# design.net
KiCad netlist of a schematic drawn in Altium Designer
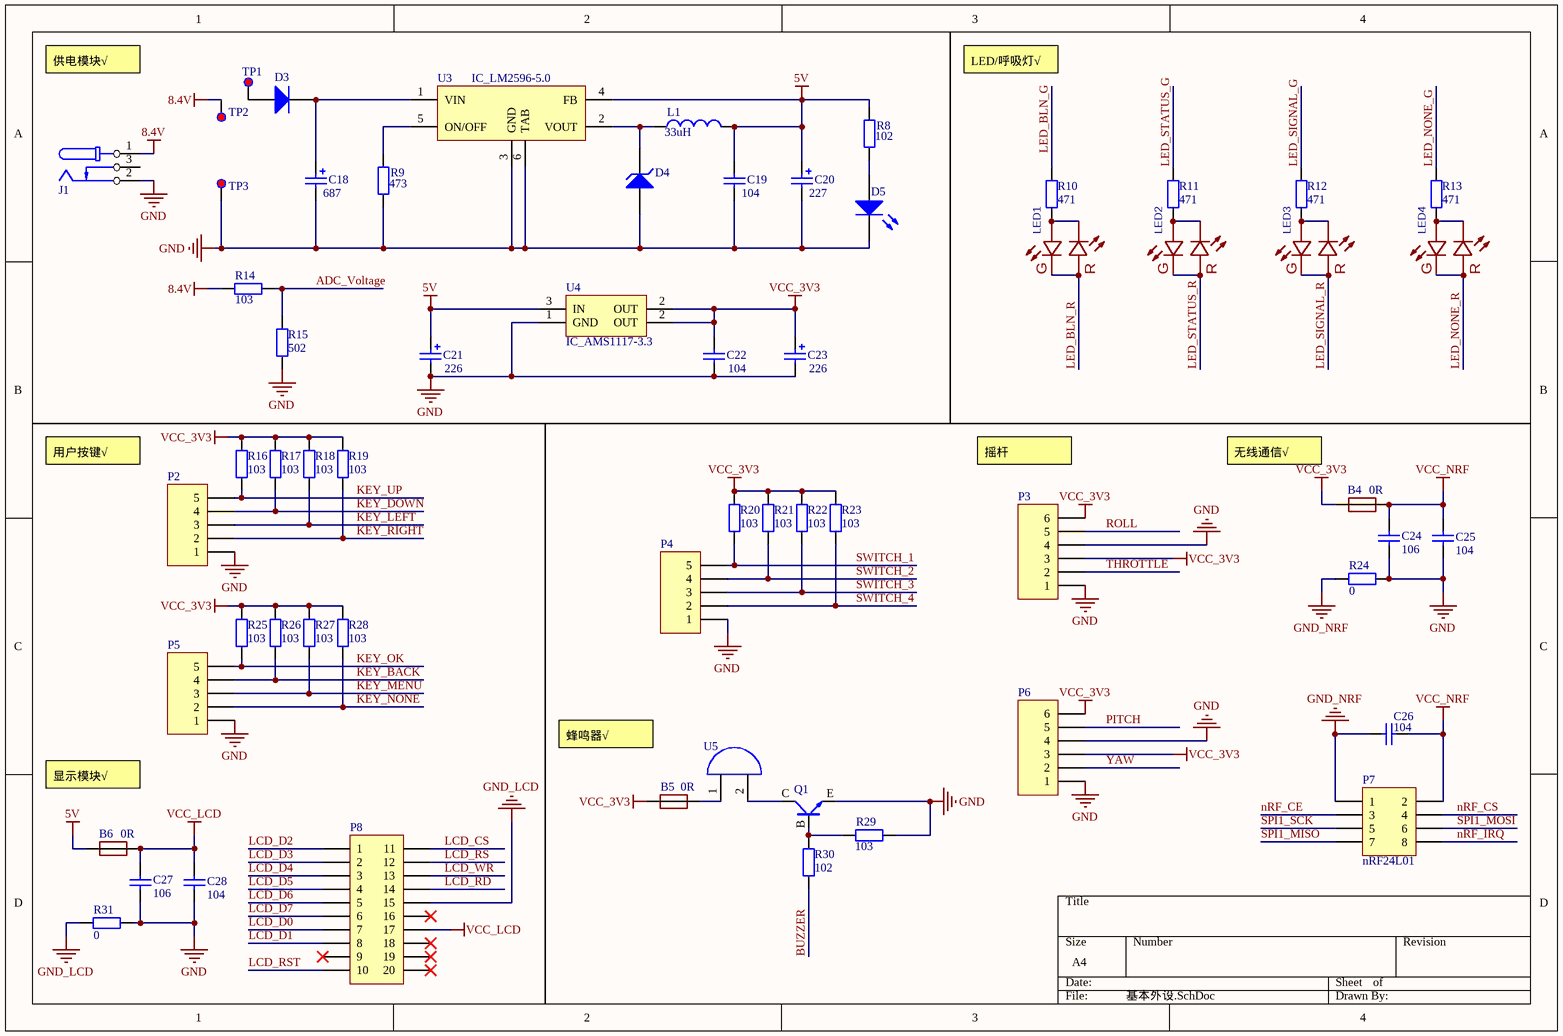
[diagram p0: 基本外设.SchDoc]

(export (version "E")
  (design (tool "Eeschema 10.0.6"))
  (components
    (comp (ref "B4")
      (value "0R")
      (footprint "CC1608-0603")
      (description "磁珠")
      (fields (field (name "Comment") "MPZ1608S101ATDH5"))
      (libsource (lib "SCHLIB") (part "FB_BEAD"))
    )
    (comp (ref "B5")
      (value "0R")
      (footprint "CC1608-0603")
      (description "磁珠")
      (fields (field (name "Comment") "MPZ1608S101ATDH5"))
      (libsource (lib "") (part "FB_BEAD_1"))
    )
    (comp (ref "B6")
      (value "0R")
      (footprint "CC1608-0603")
      (description "磁珠")
      (fields (field (name "Comment") "MPZ1608S101ATDH5"))
      (libsource (lib "SCHLIB") (part "FB_BEAD"))
    )
    (comp (ref "C18")
      (value "687")
      (footprint "CDT-10")
      (description "Polarized Capacitor (Axial)")
      (fields (field (name "Comment") "Cap Pol2") (field (name "PUBLISHER") "Altium Limited"))
      (libsource (lib "Miscellaneous Devices") (part "Cap Pol2"))
    )
    (comp (ref "C19")
      (value "104")
      (footprint "CC1608-0603")
      (description "Capacitor")
      (fields (field (name "Comment") "Cap") (field (name "PUBLISHER") "Altium Limited"))
      (libsource (lib "Miscellaneous Devices") (part "Cap"))
    )
    (comp (ref "C20")
      (value "227")
      (footprint "CDT-6.3")
      (description "Polarized Capacitor (Axial)")
      (fields (field (name "Comment") "Cap Pol2") (field (name "PUBLISHER") "Altium Limited"))
      (libsource (lib "Miscellaneous Devices") (part "Cap Pol2"))
    )
    (comp (ref "C21")
      (value "226")
      (footprint "CDT-5")
      (description "Polarized Capacitor (Axial)")
      (fields (field (name "Comment") "Cap Pol2") (field (name "PUBLISHER") "Altium Limited"))
      (libsource (lib "Miscellaneous Devices") (part "Cap Pol2"))
    )
    (comp (ref "C22")
      (value "104")
      (footprint "CC1608-0603")
      (description "Capacitor")
      (fields (field (name "Comment") "Cap") (field (name "PUBLISHER") "Altium Limited"))
      (libsource (lib "Miscellaneous Devices") (part "Cap"))
    )
    (comp (ref "C23")
      (value "226")
      (footprint "CDT-5")
      (description "Polarized Capacitor (Axial)")
      (fields (field (name "Comment") "Cap Pol2") (field (name "PUBLISHER") "Altium Limited"))
      (libsource (lib "Miscellaneous Devices") (part "Cap Pol2"))
    )
    (comp (ref "C24")
      (value "106")
      (footprint "CC1608-0603")
      (description "Capacitor")
      (fields (field (name "Comment") "Cap") (field (name "PUBLISHER") "Altium Limited"))
      (libsource (lib "Miscellaneous Devices") (part "Cap"))
    )
    (comp (ref "C25")
      (value "104")
      (footprint "CC1608-0603")
      (description "Capacitor")
      (fields (field (name "Comment") "Cap") (field (name "PUBLISHER") "Altium Limited"))
      (libsource (lib "Miscellaneous Devices") (part "Cap"))
    )
    (comp (ref "C26")
      (value "104")
      (footprint "CC1608-0603")
      (description "Capacitor")
      (fields (field (name "Comment") "Cap") (field (name "PUBLISHER") "Altium Limited"))
      (libsource (lib "Miscellaneous Devices") (part "Cap"))
    )
    (comp (ref "C27")
      (value "106")
      (footprint "CC1608-0603")
      (description "Capacitor")
      (fields (field (name "Comment") "Cap") (field (name "PUBLISHER") "Altium Limited"))
      (libsource (lib "Miscellaneous Devices") (part "Cap"))
    )
    (comp (ref "C28")
      (value "104")
      (footprint "CC1608-0603")
      (description "Capacitor")
      (fields (field (name "Comment") "Cap") (field (name "PUBLISHER") "Altium Limited"))
      (libsource (lib "Miscellaneous Devices") (part "Cap"))
    )
    (comp (ref "D3")
      (value "Diode")
      (footprint "DO-214AC(SMA)-D")
      (description "Default Diode")
      (fields (field (name "PUBLISHER") "Altium Limited"))
      (libsource (lib "Miscellaneous Devices") (part "Diode"))
    )
    (comp (ref "D4")
      (value "D Zener")
      (footprint "DO-214AC(SMA)-T")
      (description "Zener Diode")
      (fields (field (name "PUBLISHER") "Altium Limited"))
      (libsource (lib "Miscellaneous Devices") (part "D Zener"))
    )
    (comp (ref "D5")
      (value "LED0")
      (footprint "CD1608-0603")
      (description "Typical INFRARED GaAs LED")
      (fields (field (name "PUBLISHER") "Altium Limited"))
      (libsource (lib "Miscellaneous Devices") (part "LED0"))
    )
    (comp (ref "J1")
      (value "PT_POWERJACK")
      (footprint "DC2.2")
      (description "DC端子")
      (libsource (lib "SCHLIB") (part "PT_POWERJACK"))
    )
    (comp (ref "L1")
      (value "33uH")
      (footprint "L7.3X7.3X4.5")
      (description "Inductor")
      (fields (field (name "PUBLISHER") "Altium Limited"))
      (libsource (lib "Miscellaneous Devices") (part "Inductor"))
    )
    (comp (ref "LED1")
      (value "DX_LED_无极")
      (footprint "LED_无极")
      (description "无极双色发光二极管")
      (fields
        (field (name "BOM_SUPPLIER PART") "C440436")
        (field (name "BOM_MANUFACTURER PART") "TJ-L5FYTXHMNPLC2R7K-A5")
        (field (name "CONTRIBUTOR") "LCSC")
      )
      (libsource (lib "SCHLIB") (part "DX_LED_无极"))
    )
    (comp (ref "LED2")
      (value "DX_LED_无极")
      (footprint "LED_无极")
      (description "无极双色发光二极管")
      (fields
        (field (name "BOM_SUPPLIER PART") "C440436")
        (field (name "BOM_MANUFACTURER PART") "TJ-L5FYTXHMNPLC2R7K-A5")
        (field (name "CONTRIBUTOR") "LCSC")
      )
      (libsource (lib "SCHLIB") (part "DX_LED_无极"))
    )
    (comp (ref "LED3")
      (value "DX_LED_无极")
      (footprint "LED_无极")
      (description "无极双色发光二极管")
      (fields
        (field (name "BOM_SUPPLIER PART") "C440436")
        (field (name "BOM_MANUFACTURER PART") "TJ-L5FYTXHMNPLC2R7K-A5")
        (field (name "CONTRIBUTOR") "LCSC")
      )
      (libsource (lib "SCHLIB") (part "DX_LED_无极"))
    )
    (comp (ref "LED4")
      (value "DX_LED_无极")
      (footprint "LED_无极")
      (description "无极双色发光二极管")
      (fields
        (field (name "BOM_SUPPLIER PART") "C440436")
        (field (name "BOM_MANUFACTURER PART") "TJ-L5FYTXHMNPLC2R7K-A5")
        (field (name "CONTRIBUTOR") "LCSC")
      )
      (libsource (lib "SCHLIB") (part "DX_LED_无极"))
    )
    (comp (ref "P2")
      (value "Header 5")
      (footprint "XHT_1.25_SMD_5p")
      (description "Header, 5-Pin")
      (fields (field (name "PUBLISHER") "Altium Limited"))
      (libsource (lib "Miscellaneous Connectors") (part "Header 5"))
    )
    (comp (ref "P3")
      (value "Header 6")
      (footprint "XHT_2.0_SMD_6P")
      (description "Header, 6-Pin")
      (fields (field (name "PUBLISHER") "Altium Limited"))
      (libsource (lib "Miscellaneous Connectors") (part "Header 6"))
    )
    (comp (ref "P4")
      (value "Header 6")
      (footprint "XHT_1.25_SMD_5p")
      (description "Header, 5-Pin")
      (fields (field (name "PUBLISHER") "Altium Limited"))
      (libsource (lib "Miscellaneous Connectors") (part "Header 5"))
    )
    (comp (ref "P5")
      (value "Header 5")
      (footprint "XHT_1.25_SMD_5p")
      (description "Header, 5-Pin")
      (fields (field (name "PUBLISHER") "Altium Limited"))
      (libsource (lib "Miscellaneous Connectors") (part "Header 5"))
    )
    (comp (ref "P6")
      (value "Header 6")
      (footprint "XHT_2.0_SMD_6P")
      (description "Header, 6-Pin")
      (fields (field (name "PUBLISHER") "Altium Limited"))
      (libsource (lib "Miscellaneous Connectors") (part "Header 6"))
    )
    (comp (ref "P7")
      (value "nRF24L01")
      (footprint "HDR2X4")
      (description "Header, 4-Pin, Dual row")
      (fields (field (name "PUBLISHER") "Altium Limited"))
      (libsource (lib "Miscellaneous Connectors") (part "Header 4X2"))
    )
    (comp (ref "P8")
      (value "Header 10X2A")
      (footprint "LCD_2.4_TFT")
      (description "Header, 10-Pin, Dual row")
      (fields (field (name "PUBLISHER") "Altium Limited"))
      (libsource (lib "Miscellaneous Connectors") (part "Header 10X2A"))
    )
    (comp (ref "Q1")
      (value "TX_NPN")
      (footprint "SOT-23-3T")
      (description "NPN三极管")
      (libsource (lib "SCHLIB") (part "TX_NPN"))
    )
    (comp (ref "R8")
      (value "102")
      (footprint "CC1608-0603")
      (description "Resistor")
      (fields (field (name "Comment") "Res2") (field (name "PUBLISHER") "Altium Limited"))
      (libsource (lib "") (part "Res2_2"))
    )
    (comp (ref "R9")
      (value "473")
      (footprint "CC1608-0603")
      (description "Resistor")
      (fields (field (name "Comment") "Res2") (field (name "PUBLISHER") "Altium Limited"))
      (libsource (lib "") (part "Res2_2"))
    )
    (comp (ref "R10")
      (value "471")
      (footprint "CC1608-0603")
      (description "电阻")
      (fields (field (name "Comment") "RX_RES"))
      (libsource (lib "") (part "RX_RES_2"))
    )
    (comp (ref "R11")
      (value "471")
      (footprint "CC1608-0603")
      (description "电阻")
      (fields (field (name "Comment") "RX_RES"))
      (libsource (lib "") (part "RX_RES_2"))
    )
    (comp (ref "R12")
      (value "471")
      (footprint "CC1608-0603")
      (description "电阻")
      (fields (field (name "Comment") "RX_RES"))
      (libsource (lib "") (part "RX_RES_2"))
    )
    (comp (ref "R13")
      (value "471")
      (footprint "CC1608-0603")
      (description "电阻")
      (fields (field (name "Comment") "RX_RES"))
      (libsource (lib "") (part "RX_RES_2"))
    )
    (comp (ref "R14")
      (value "103")
      (footprint "CC1608-0603")
      (description "Resistor")
      (fields (field (name "Comment") "Res2") (field (name "PUBLISHER") "Altium Limited"))
      (libsource (lib "") (part "Res2_1"))
    )
    (comp (ref "R15")
      (value "502")
      (footprint "CC1608-0603")
      (description "Resistor")
      (fields (field (name "Comment") "Res2") (field (name "PUBLISHER") "Altium Limited"))
      (libsource (lib "Miscellaneous Devices") (part "Res2"))
    )
    (comp (ref "R16")
      (value "103")
      (footprint "CC1608-0603")
      (description "电阻")
      (fields (field (name "Comment") "RX_RES"))
      (libsource (lib "SCHLIB") (part "RX_RES"))
    )
    (comp (ref "R17")
      (value "103")
      (footprint "CC1608-0603")
      (description "电阻")
      (fields (field (name "Comment") "RX_RES"))
      (libsource (lib "SCHLIB") (part "RX_RES"))
    )
    (comp (ref "R18")
      (value "103")
      (footprint "CC1608-0603")
      (description "电阻")
      (fields (field (name "Comment") "RX_RES"))
      (libsource (lib "SCHLIB") (part "RX_RES"))
    )
    (comp (ref "R19")
      (value "103")
      (footprint "CC1608-0603")
      (description "电阻")
      (fields (field (name "Comment") "RX_RES"))
      (libsource (lib "SCHLIB") (part "RX_RES"))
    )
    (comp (ref "R20")
      (value "103")
      (footprint "CC1608-0603")
      (description "电阻")
      (fields (field (name "Comment") "RX_RES"))
      (libsource (lib "SCHLIB") (part "RX_RES"))
    )
    (comp (ref "R21")
      (value "103")
      (footprint "CC1608-0603")
      (description "电阻")
      (fields (field (name "Comment") "RX_RES"))
      (libsource (lib "SCHLIB") (part "RX_RES"))
    )
    (comp (ref "R22")
      (value "103")
      (footprint "CC1608-0603")
      (description "电阻")
      (fields (field (name "Comment") "RX_RES"))
      (libsource (lib "SCHLIB") (part "RX_RES"))
    )
    (comp (ref "R23")
      (value "103")
      (footprint "CC1608-0603")
      (description "电阻")
      (fields (field (name "Comment") "RX_RES"))
      (libsource (lib "SCHLIB") (part "RX_RES"))
    )
    (comp (ref "R24")
      (value "0")
      (footprint "CC1608-0603")
      (description "电阻")
      (fields (field (name "Comment") "RX_RES"))
      (libsource (lib "") (part "RX_RES_1"))
    )
    (comp (ref "R25")
      (value "103")
      (footprint "CC1608-0603")
      (description "电阻")
      (fields (field (name "Comment") "RX_RES"))
      (libsource (lib "SCHLIB") (part "RX_RES"))
    )
    (comp (ref "R26")
      (value "103")
      (footprint "CC1608-0603")
      (description "电阻")
      (fields (field (name "Comment") "RX_RES"))
      (libsource (lib "SCHLIB") (part "RX_RES"))
    )
    (comp (ref "R27")
      (value "103")
      (footprint "CC1608-0603")
      (description "电阻")
      (fields (field (name "Comment") "RX_RES"))
      (libsource (lib "SCHLIB") (part "RX_RES"))
    )
    (comp (ref "R28")
      (value "103")
      (footprint "CC1608-0603")
      (description "电阻")
      (fields (field (name "Comment") "RX_RES"))
      (libsource (lib "SCHLIB") (part "RX_RES"))
    )
    (comp (ref "R29")
      (value "103")
      (footprint "CC1608-0603")
      (description "电阻")
      (fields (field (name "Comment") "RX_RES"))
      (libsource (lib "") (part "RX_RES_3"))
    )
    (comp (ref "R30")
      (value "102")
      (footprint "CC1608-0603")
      (description "电阻")
      (fields (field (name "Comment") "RX_RES"))
      (libsource (lib "") (part "RX_RES_2"))
    )
    (comp (ref "R31")
      (value "0")
      (footprint "CC1608-0603")
      (description "电阻")
      (fields (field (name "Comment") "RX_RES"))
      (libsource (lib "") (part "RX_RES_1"))
    )
    (comp (ref "TP1")
      (value "PT_TESTPOINT")
      (footprint "TP-SMD")
      (description "测试点")
      (libsource (lib "SCHLIB") (part "PT_TESTPOINT"))
    )
    (comp (ref "TP2")
      (value "PT_TESTPOINT")
      (footprint "TP-SMD")
      (description "测试点")
      (libsource (lib "SCHLIB") (part "PT_TESTPOINT"))
    )
    (comp (ref "TP3")
      (value "PT_TESTPOINT")
      (footprint "TP-SMD")
      (description "测试点")
      (libsource (lib "SCHLIB") (part "PT_TESTPOINT"))
    )
    (comp (ref "U3")
      (value "IC_LM2596-5.0")
      (footprint "TO-263-5")
      (description "电源芯片")
      (libsource (lib "SCHLIB") (part "IC_LM2596"))
    )
    (comp (ref "U4")
      (value "IC_AMS1117-3.3")
      (footprint "SOT-223")
      (description "电源芯片")
      (libsource (lib "SCHLIB") (part "IC_AMS1117"))
    )
    (comp (ref "U5")
      (value "SC_BEEP")
      (footprint "SC_Buzzer")
      (description "蜂鸣器")
      (libsource (lib "SCHLIB") (part "SC_BEEP"))
    )
  )
  (nets
    (net (code "1") (name "/ADC_Voltage") (class "Default")
      (node (ref "R14") (pin "1") (pinfunction "1_1") (pintype "passive"))
      (node (ref "R15") (pin "1") (pinfunction "1_1") (pintype "passive"))
    )
    (net (code "2") (name "/BUZZER") (class "Default")
      (node (ref "R30") (pin "1") (pinfunction "1_1") (pintype "passive"))
    )
    (net (code "3") (name "/KEY_BACK") (class "Default")
      (node (ref "P5") (pin "4") (pinfunction "4_4") (pintype "passive"))
      (node (ref "R26") (pin "2") (pinfunction "2_2") (pintype "passive"))
    )
    (net (code "4") (name "/KEY_DOWN") (class "Default")
      (node (ref "P2") (pin "4") (pinfunction "4_4") (pintype "passive"))
      (node (ref "R17") (pin "2") (pinfunction "2_2") (pintype "passive"))
    )
    (net (code "5") (name "/KEY_LEFT") (class "Default")
      (node (ref "P2") (pin "3") (pinfunction "3_3") (pintype "passive"))
      (node (ref "R18") (pin "2") (pinfunction "2_2") (pintype "passive"))
    )
    (net (code "6") (name "/KEY_MENU") (class "Default")
      (node (ref "P5") (pin "3") (pinfunction "3_3") (pintype "passive"))
      (node (ref "R27") (pin "2") (pinfunction "2_2") (pintype "passive"))
    )
    (net (code "7") (name "/KEY_NONE") (class "Default")
      (node (ref "P5") (pin "2") (pinfunction "2_2") (pintype "passive"))
      (node (ref "R28") (pin "2") (pinfunction "2_2") (pintype "passive"))
    )
    (net (code "8") (name "/KEY_OK") (class "Default")
      (node (ref "P5") (pin "5") (pinfunction "5_5") (pintype "passive"))
      (node (ref "R25") (pin "2") (pinfunction "2_2") (pintype "passive"))
    )
    (net (code "9") (name "/KEY_RIGHT") (class "Default")
      (node (ref "P2") (pin "2") (pinfunction "2_2") (pintype "passive"))
      (node (ref "R19") (pin "2") (pinfunction "2_2") (pintype "passive"))
    )
    (net (code "10") (name "/KEY_UP") (class "Default")
      (node (ref "P2") (pin "5") (pinfunction "5_5") (pintype "passive"))
      (node (ref "R16") (pin "2") (pinfunction "2_2") (pintype "passive"))
    )
    (net (code "11") (name "/LCD_CS") (class "Default")
      (node (ref "P8") (pin "11") (pinfunction "11_11") (pintype "passive"))
    )
    (net (code "12") (name "/LCD_D0") (class "Default")
      (node (ref "P8") (pin "7") (pinfunction "7_7") (pintype "passive"))
    )
    (net (code "13") (name "/LCD_D1") (class "Default")
      (node (ref "P8") (pin "8") (pinfunction "8_8") (pintype "passive"))
    )
    (net (code "14") (name "/LCD_D2") (class "Default")
      (node (ref "P8") (pin "1") (pinfunction "1_1") (pintype "passive"))
    )
    (net (code "15") (name "/LCD_D3") (class "Default")
      (node (ref "P8") (pin "2") (pinfunction "2_2") (pintype "passive"))
    )
    (net (code "16") (name "/LCD_D4") (class "Default")
      (node (ref "P8") (pin "3") (pinfunction "3_3") (pintype "passive"))
    )
    (net (code "17") (name "/LCD_D5") (class "Default")
      (node (ref "P8") (pin "4") (pinfunction "4_4") (pintype "passive"))
    )
    (net (code "18") (name "/LCD_D6") (class "Default")
      (node (ref "P8") (pin "5") (pinfunction "5_5") (pintype "passive"))
    )
    (net (code "19") (name "/LCD_D7") (class "Default")
      (node (ref "P8") (pin "6") (pinfunction "6_6") (pintype "passive"))
    )
    (net (code "20") (name "/LCD_RD") (class "Default")
      (node (ref "P8") (pin "14") (pinfunction "14_14") (pintype "passive"))
    )
    (net (code "21") (name "/LCD_RS") (class "Default")
      (node (ref "P8") (pin "12") (pinfunction "12_12") (pintype "passive"))
    )
    (net (code "22") (name "/LCD_RST") (class "Default")
      (node (ref "P8") (pin "10") (pinfunction "10_10") (pintype "passive"))
    )
    (net (code "23") (name "/LCD_WR") (class "Default")
      (node (ref "P8") (pin "13") (pinfunction "13_13") (pintype "passive"))
    )
    (net (code "24") (name "/LED_BLN_G") (class "Default")
      (node (ref "R10") (pin "2") (pinfunction "2_2") (pintype "passive"))
    )
    (net (code "25") (name "/LED_BLN_R") (class "Default")
      (node (ref "LED1") (pin "1") (pinfunction "-_1") (pintype "passive"))
    )
    (net (code "26") (name "/LED_NONE_G") (class "Default")
      (node (ref "R13") (pin "2") (pinfunction "2_2") (pintype "passive"))
    )
    (net (code "27") (name "/LED_NONE_R") (class "Default")
      (node (ref "LED4") (pin "1") (pinfunction "-_1") (pintype "passive"))
    )
    (net (code "28") (name "/LED_SIGNAL_G") (class "Default")
      (node (ref "R12") (pin "2") (pinfunction "2_2") (pintype "passive"))
    )
    (net (code "29") (name "/LED_SIGNAL_R") (class "Default")
      (node (ref "LED3") (pin "1") (pinfunction "-_1") (pintype "passive"))
    )
    (net (code "30") (name "/LED_STATUS_G") (class "Default")
      (node (ref "R11") (pin "2") (pinfunction "2_2") (pintype "passive"))
    )
    (net (code "31") (name "/LED_STATUS_R") (class "Default")
      (node (ref "LED2") (pin "1") (pinfunction "-_1") (pintype "passive"))
    )
    (net (code "32") (name "/PITCH") (class "Default")
      (node (ref "P6") (pin "5") (pinfunction "5_5") (pintype "passive"))
    )
    (net (code "33") (name "/ROLL") (class "Default")
      (node (ref "P3") (pin "5") (pinfunction "5_5") (pintype "passive"))
    )
    (net (code "34") (name "/SPI1_MISO") (class "Default")
      (node (ref "P7") (pin "7") (pinfunction "7_7") (pintype "passive"))
    )
    (net (code "35") (name "/SPI1_MOSI") (class "Default")
      (node (ref "P7") (pin "6") (pinfunction "6_6") (pintype "passive"))
    )
    (net (code "36") (name "/SPI1_SCK") (class "Default")
      (node (ref "P7") (pin "5") (pinfunction "5_5") (pintype "passive"))
    )
    (net (code "37") (name "/SWITCH_1") (class "Default")
      (node (ref "P4") (pin "5") (pinfunction "5_5") (pintype "passive"))
      (node (ref "R20") (pin "2") (pinfunction "2_2") (pintype "passive"))
    )
    (net (code "38") (name "/SWITCH_2") (class "Default")
      (node (ref "P4") (pin "4") (pinfunction "4_4") (pintype "passive"))
      (node (ref "R21") (pin "2") (pinfunction "2_2") (pintype "passive"))
    )
    (net (code "39") (name "/SWITCH_3") (class "Default")
      (node (ref "P4") (pin "3") (pinfunction "3_3") (pintype "passive"))
      (node (ref "R22") (pin "2") (pinfunction "2_2") (pintype "passive"))
    )
    (net (code "40") (name "/SWITCH_4") (class "Default")
      (node (ref "P4") (pin "2") (pinfunction "2_2") (pintype "passive"))
      (node (ref "R23") (pin "2") (pinfunction "2_2") (pintype "passive"))
    )
    (net (code "41") (name "/THROTTLE") (class "Default")
      (node (ref "P3") (pin "2") (pinfunction "2_2") (pintype "passive"))
    )
    (net (code "42") (name "/YAW") (class "Default")
      (node (ref "P6") (pin "2") (pinfunction "2_2") (pintype "passive"))
    )
    (net (code "43") (name "/nRF_CE") (class "Default")
      (node (ref "P7") (pin "3") (pinfunction "3_3") (pintype "passive"))
    )
    (net (code "44") (name "/nRF_CS") (class "Default")
      (node (ref "P7") (pin "4") (pinfunction "4_4") (pintype "passive"))
    )
    (net (code "45") (name "/nRF_IRQ") (class "Default")
      (node (ref "P7") (pin "8") (pinfunction "8_8") (pintype "passive"))
    )
    (net (code "46") (name "5V") (class "Default")
      (node (ref "B6") (pin "1") (pinfunction "1_1") (pintype "passive"))
      (node (ref "C19") (pin "2") (pinfunction "2_2") (pintype "passive"))
      (node (ref "C20") (pin "1") (pinfunction "1_1") (pintype "passive"))
      (node (ref "C21") (pin "1") (pinfunction "1_1") (pintype "passive"))
      (node (ref "L1") (pin "2") (pinfunction "2_2") (pintype "passive"))
      (node (ref "R8") (pin "2") (pinfunction "2_2") (pintype "passive"))
      (node (ref "U3") (pin "4") (pinfunction "FB_4") (pintype "passive"))
      (node (ref "U4") (pin "3") (pinfunction "IN_3") (pintype "passive"))
    )
    (net (code "47") (name "8.4V") (class "Default")
      (node (ref "J1") (pin "1") (pinfunction "1_1") (pintype "passive"))
      (node (ref "R14") (pin "2") (pinfunction "2_2") (pintype "passive"))
      (node (ref "TP2") (pin "1") (pinfunction "1_1") (pintype "passive"))
    )
    (net (code "48") (name "GND") (class "Default")
      (node (ref "C18") (pin "2") (pinfunction "2_2") (pintype "passive"))
      (node (ref "C19") (pin "1") (pinfunction "1_1") (pintype "passive"))
      (node (ref "C20") (pin "2") (pinfunction "2_2") (pintype "passive"))
      (node (ref "C21") (pin "2") (pinfunction "2_2") (pintype "passive"))
      (node (ref "C22") (pin "1") (pinfunction "1_1") (pintype "passive"))
      (node (ref "C23") (pin "2") (pinfunction "2_2") (pintype "passive"))
      (node (ref "C24") (pin "1") (pinfunction "1_1") (pintype "passive"))
      (node (ref "C25") (pin "1") (pinfunction "1_1") (pintype "passive"))
      (node (ref "C27") (pin "1") (pinfunction "1_1") (pintype "passive"))
      (node (ref "C28") (pin "1") (pinfunction "1_1") (pintype "passive"))
      (node (ref "D4") (pin "1") (pinfunction "A_1") (pintype "passive"))
      (node (ref "D5") (pin "2") (pinfunction "K_2") (pintype "passive"))
      (node (ref "J1") (pin "2") (pinfunction "2_2") (pintype "passive"))
      (node (ref "P2") (pin "1") (pinfunction "1_1") (pintype "passive"))
      (node (ref "P3") (pin "1") (pinfunction "1_1") (pintype "passive"))
      (node (ref "P3") (pin "4") (pinfunction "4_4") (pintype "passive"))
      (node (ref "P4") (pin "1") (pinfunction "1_1") (pintype "passive"))
      (node (ref "P5") (pin "1") (pinfunction "1_1") (pintype "passive"))
      (node (ref "P6") (pin "1") (pinfunction "1_1") (pintype "passive"))
      (node (ref "P6") (pin "4") (pinfunction "4_4") (pintype "passive"))
      (node (ref "Q1") (pin "E") (pinfunction "E_E") (pintype "passive"))
      (node (ref "R15") (pin "2") (pinfunction "2_2") (pintype "passive"))
      (node (ref "R24") (pin "2") (pinfunction "2_2") (pintype "passive"))
      (node (ref "R29") (pin "1") (pinfunction "1_1") (pintype "passive"))
      (node (ref "R31") (pin "2") (pinfunction "2_2") (pintype "passive"))
      (node (ref "R9") (pin "1") (pinfunction "1_1") (pintype "passive"))
      (node (ref "TP3") (pin "1") (pinfunction "1_1") (pintype "passive"))
      (node (ref "U3") (pin "3") (pinfunction "GND_3") (pintype "passive"))
      (node (ref "U3") (pin "6") (pinfunction "TAB_6") (pintype "passive"))
      (node (ref "U4") (pin "1") (pinfunction "GND_1") (pintype "passive"))
    )
    (net (code "49") (name "GND_LCD") (class "Default")
      (node (ref "P8") (pin "15") (pinfunction "15_15") (pintype "passive"))
      (node (ref "R31") (pin "1") (pinfunction "1_1") (pintype "passive"))
    )
    (net (code "50") (name "GND_NRF") (class "Default")
      (node (ref "C26") (pin "2") (pinfunction "2_2") (pintype "passive"))
      (node (ref "P7") (pin "1") (pinfunction "1_1") (pintype "passive"))
      (node (ref "R24") (pin "1") (pinfunction "1_1") (pintype "passive"))
    )
    (net (code "51") (name "Net-(B5-Pad1)") (class "Default")
      (node (ref "B5") (pin "1") (pinfunction "1_1") (pintype "passive"))
      (node (ref "U5") (pin "1") (pinfunction "1_1") (pintype "passive"))
    )
    (net (code "52") (name "Net-(D3-A)") (class "Default")
      (node (ref "D3") (pin "1") (pinfunction "A_1") (pintype "passive"))
      (node (ref "TP1") (pin "1") (pinfunction "1_1") (pintype "passive"))
    )
    (net (code "53") (name "Net-(D3-K)") (class "Default")
      (node (ref "C18") (pin "1") (pinfunction "1_1") (pintype "passive"))
      (node (ref "D3") (pin "2") (pinfunction "K_2") (pintype "passive"))
      (node (ref "U3") (pin "1") (pinfunction "VIN_1") (pintype "passive"))
    )
    (net (code "54") (name "Net-(D4-K)") (class "Default")
      (node (ref "D4") (pin "2") (pinfunction "K_2") (pintype "passive"))
      (node (ref "L1") (pin "1") (pinfunction "1_1") (pintype "passive"))
      (node (ref "U3") (pin "2") (pinfunction "VOUT_2") (pintype "passive"))
    )
    (net (code "55") (name "Net-(D5-A)") (class "Default")
      (node (ref "D5") (pin "1") (pinfunction "A_1") (pintype "passive"))
      (node (ref "R8") (pin "1") (pinfunction "1_1") (pintype "passive"))
    )
    (net (code "56") (name "Net-(LED1-+-Pad2)") (class "Default")
      (node (ref "LED1") (pin "2") (pinfunction "+_2") (pintype "passive"))
      (node (ref "R10") (pin "1") (pinfunction "1_1") (pintype "passive"))
    )
    (net (code "57") (name "Net-(LED2-+-Pad2)") (class "Default")
      (node (ref "LED2") (pin "2") (pinfunction "+_2") (pintype "passive"))
      (node (ref "R11") (pin "1") (pinfunction "1_1") (pintype "passive"))
    )
    (net (code "58") (name "Net-(LED3-+-Pad2)") (class "Default")
      (node (ref "LED3") (pin "2") (pinfunction "+_2") (pintype "passive"))
      (node (ref "R12") (pin "1") (pinfunction "1_1") (pintype "passive"))
    )
    (net (code "59") (name "Net-(LED4-+-Pad2)") (class "Default")
      (node (ref "LED4") (pin "2") (pinfunction "+_2") (pintype "passive"))
      (node (ref "R13") (pin "1") (pinfunction "1_1") (pintype "passive"))
    )
    (net (code "60") (name "Net-(Q1-PadB)") (class "Default")
      (node (ref "Q1") (pin "B") (pinfunction "B_B") (pintype "passive"))
      (node (ref "R29") (pin "2") (pinfunction "2_2") (pintype "passive"))
      (node (ref "R30") (pin "2") (pinfunction "2_2") (pintype "passive"))
    )
    (net (code "61") (name "Net-(Q1-PadC)") (class "Default")
      (node (ref "Q1") (pin "C") (pinfunction "C_C") (pintype "passive"))
      (node (ref "U5") (pin "2") (pinfunction "2_2") (pintype "passive"))
    )
    (net (code "62") (name "Net-(U3-ON{slash}OFF)") (class "Default")
      (node (ref "R9") (pin "2") (pinfunction "2_2") (pintype "passive"))
      (node (ref "U3") (pin "5") (pinfunction "ON/OFF_5") (pintype "passive"))
    )
    (net (code "63") (name "VCC_3V3") (class "Default")
      (node (ref "B4") (pin "1") (pinfunction "1_1") (pintype "passive"))
      (node (ref "B5") (pin "2") (pinfunction "2_2") (pintype "passive"))
      (node (ref "C22") (pin "2") (pinfunction "2_2") (pintype "passive"))
      (node (ref "C23") (pin "1") (pinfunction "1_1") (pintype "passive"))
      (node (ref "P3") (pin "3") (pinfunction "3_3") (pintype "passive"))
      (node (ref "P3") (pin "6") (pinfunction "6_6") (pintype "passive"))
      (node (ref "P6") (pin "3") (pinfunction "3_3") (pintype "passive"))
      (node (ref "P6") (pin "6") (pinfunction "6_6") (pintype "passive"))
      (node (ref "R16") (pin "1") (pinfunction "1_1") (pintype "passive"))
      (node (ref "R17") (pin "1") (pinfunction "1_1") (pintype "passive"))
      (node (ref "R18") (pin "1") (pinfunction "1_1") (pintype "passive"))
      (node (ref "R19") (pin "1") (pinfunction "1_1") (pintype "passive"))
      (node (ref "R20") (pin "1") (pinfunction "1_1") (pintype "passive"))
      (node (ref "R21") (pin "1") (pinfunction "1_1") (pintype "passive"))
      (node (ref "R22") (pin "1") (pinfunction "1_1") (pintype "passive"))
      (node (ref "R23") (pin "1") (pinfunction "1_1") (pintype "passive"))
      (node (ref "R25") (pin "1") (pinfunction "1_1") (pintype "passive"))
      (node (ref "R26") (pin "1") (pinfunction "1_1") (pintype "passive"))
      (node (ref "R27") (pin "1") (pinfunction "1_1") (pintype "passive"))
      (node (ref "R28") (pin "1") (pinfunction "1_1") (pintype "passive"))
      (node (ref "U4") (pin "2") (pinfunction "OUT_2") (pintype "passive"))
    )
    (net (code "64") (name "VCC_LCD") (class "Default")
      (node (ref "B6") (pin "2") (pinfunction "2_2") (pintype "passive"))
      (node (ref "C27") (pin "2") (pinfunction "2_2") (pintype "passive"))
      (node (ref "C28") (pin "2") (pinfunction "2_2") (pintype "passive"))
      (node (ref "P8") (pin "17") (pinfunction "17_17") (pintype "passive"))
    )
    (net (code "65") (name "VCC_NRF") (class "Default")
      (node (ref "B4") (pin "2") (pinfunction "2_2") (pintype "passive"))
      (node (ref "C24") (pin "2") (pinfunction "2_2") (pintype "passive"))
      (node (ref "C25") (pin "2") (pinfunction "2_2") (pintype "passive"))
      (node (ref "C26") (pin "1") (pinfunction "1_1") (pintype "passive"))
      (node (ref "P7") (pin "2") (pinfunction "2_2") (pintype "passive"))
    )
    (net (code "66") (name "unconnected-(J1-Pad3)") (class "Default")
      (node (ref "J1") (pin "3") (pinfunction "3_3") (pintype "passive"))
    )
    (net (code "67") (name "unconnected-(P8-Pad9)") (class "Default")
      (node (ref "P8") (pin "9") (pinfunction "9_9") (pintype "passive+no_connect"))
    )
    (net (code "68") (name "unconnected-(P8-Pad16)") (class "Default")
      (node (ref "P8") (pin "16") (pinfunction "16_16") (pintype "passive+no_connect"))
    )
    (net (code "69") (name "unconnected-(P8-Pad18)") (class "Default")
      (node (ref "P8") (pin "18") (pinfunction "18_18") (pintype "passive+no_connect"))
    )
    (net (code "70") (name "unconnected-(P8-Pad19)") (class "Default")
      (node (ref "P8") (pin "19") (pinfunction "19_19") (pintype "passive+no_connect"))
    )
    (net (code "71") (name "unconnected-(P8-Pad20)") (class "Default")
      (node (ref "P8") (pin "20") (pinfunction "20_20") (pintype "passive+no_connect"))
    )
  )
)
